# IVC_INTEGRATOR.net
KiCad netlist of a schematic drawn in Altium Designer
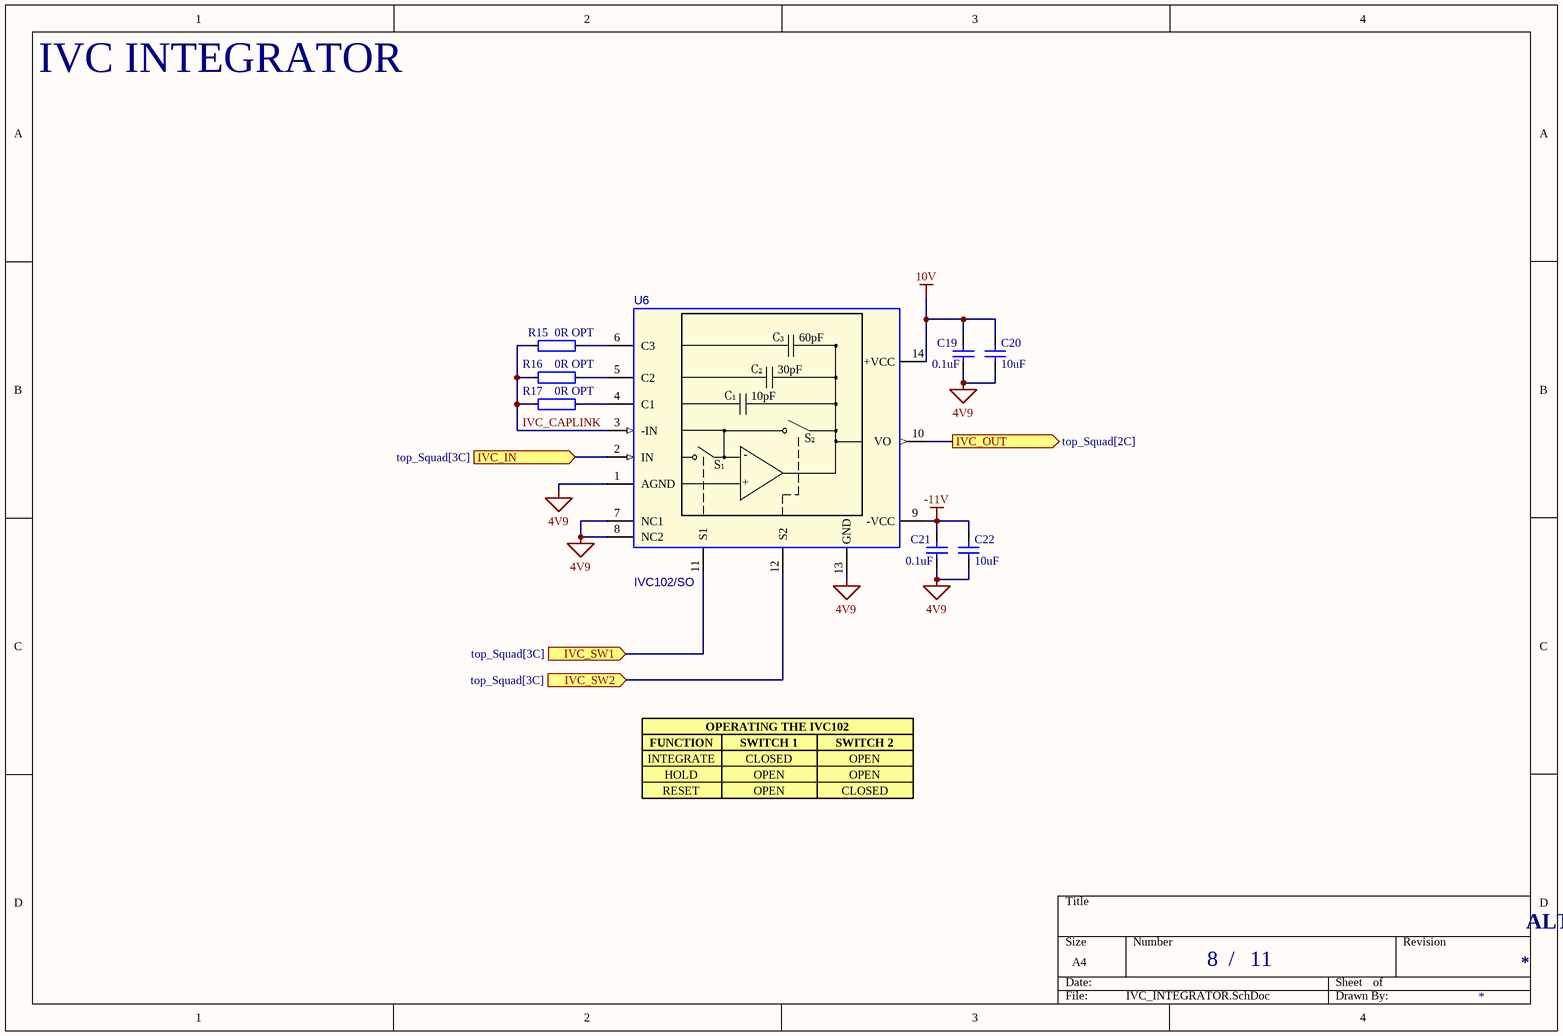
[diagram p0: IVC_INTEGRATOR.SchDoc]

(export (version "E")
  (design (tool "Eeschema 10.0.6"))
  (components
    (comp (ref "C19")
      (value "0.1uF")
      (footprint "CAP 0603 NON-IPC KEMET X7R")
      (description "Kemet C0603C104K5RACAUTO - Cap Ceramic 0.1uF 50V X7R 10% 0603 125C Paper T/R")
      (fields (field (name "MF") "Kemet") (field (name "MP") "C0603C104K5RACAUTO"))
      (libsource (lib "ALTAIR_PD_Capacitors") (part "CAP"))
    )
    (comp (ref "C20")
      (value "10uF")
      (footprint "CAP 0805 IPC MID DENSITY")
      (description "Murata GRM21BR61E106KA73L - Cap Ceramic 10uF 10% 25V X5R 0805")
      (fields (field (name "MF") "Murata") (field (name "MP") "GRM21BR61E106KA73L"))
      (libsource (lib "ALTAIR_PD_Capacitors") (part "CAP"))
    )
    (comp (ref "C21")
      (value "0.1uF")
      (footprint "CAP 0603 NON-IPC KEMET X7R")
      (description "Kemet C0603C104K5RACAUTO - Cap Ceramic 0.1uF 50V X7R 10% 0603 125C Paper T/R")
      (fields (field (name "MF") "Kemet") (field (name "MP") "C0603C104K5RACAUTO"))
      (libsource (lib "ALTAIR_PD_Capacitors") (part "CAP"))
    )
    (comp (ref "C22")
      (value "10uF")
      (footprint "CAP 0805 IPC MID DENSITY")
      (description "Murata GRM21BR61E106KA73L - Cap Ceramic 10uF 10% 25V X5R 0805")
      (fields (field (name "MF") "Murata") (field (name "MP") "GRM21BR61E106KA73L"))
      (libsource (lib "ALTAIR_PD_Capacitors") (part "CAP"))
    )
    (comp (ref "R15")
      (value "0R OPT")
      (footprint "RES 0402 IPC LOW DENSITY")
      (description "Yageo RC0402JR-070RL - Res 0 Ohms 1/16W SMD 0402")
      (fields (field (name "MF") "YAGEO") (field (name "MP") "RC0402JR-070RL"))
      (libsource (lib "ALTAIR_PD_Resistors") (part "IMPEDANCE"))
    )
    (comp (ref "R16")
      (value "0R OPT")
      (footprint "RES 0402 IPC LOW DENSITY")
      (description "Yageo RC0402JR-070RL - Res 0 Ohms 1/16W SMD 0402")
      (fields (field (name "MF") "YAGEO") (field (name "MP") "RC0402JR-070RL"))
      (libsource (lib "ALTAIR_PD_Resistors") (part "IMPEDANCE"))
    )
    (comp (ref "R17")
      (value "0R OPT")
      (footprint "RES 0402 IPC LOW DENSITY")
      (description "Yageo RC0402JR-070RL - Res 0 Ohms 1/16W SMD 0402")
      (fields (field (name "MF") "YAGEO") (field (name "MP") "RC0402JR-070RL"))
      (libsource (lib "ALTAIR_PD_Resistors") (part "IMPEDANCE"))
    )
    (comp (ref "U6")
      (value "IVC102/SO")
      (footprint "14-SOIC 4MM WIDE LOW DENSITY")
      (description "Precision Switched Integrator Transimpedance Amplifier")
      (fields (field (name "MF") "Texas Instruments") (field (name "MP") "IVC102U"))
      (libsource (lib "ALTAIR_PD_Amplifiers") (part "IVC102/SO_5"))
    )
  )
  (nets
    (net (code "1") (name "-11V") (class "Default")
      (node (ref "C21") (pin "2") (pinfunction "2_2") (pintype "passive"))
      (node (ref "C22") (pin "2") (pinfunction "2_2") (pintype "passive"))
      (node (ref "U6") (pin "9") (pinfunction "-VCC_9") (pintype "power_in"))
    )
    (net (code "2") (name "/IVC_CAPLINK") (class "Default")
      (node (ref "R15") (pin "1") (pinfunction "1_1") (pintype "passive"))
      (node (ref "R16") (pin "1") (pinfunction "1_1") (pintype "passive"))
      (node (ref "R17") (pin "1") (pinfunction "1_1") (pintype "passive"))
      (node (ref "U6") (pin "3") (pinfunction "-IN_3") (pintype "input"))
    )
    (net (code "3") (name "/IVC_IN") (class "Default")
      (node (ref "U6") (pin "2") (pinfunction "IN_2") (pintype "input"))
    )
    (net (code "4") (name "/IVC_OUT") (class "Default")
      (node (ref "U6") (pin "10") (pinfunction "VO_10") (pintype "output"))
    )
    (net (code "5") (name "/IVC_SW1") (class "Default")
      (node (ref "U6") (pin "11") (pinfunction "S1_11") (pintype "passive"))
    )
    (net (code "6") (name "/IVC_SW2") (class "Default")
      (node (ref "U6") (pin "12") (pinfunction "S2_12") (pintype "passive"))
    )
    (net (code "7") (name "4V9") (class "Default")
      (node (ref "C19") (pin "1") (pinfunction "1_1") (pintype "passive"))
      (node (ref "C20") (pin "1") (pinfunction "1_1") (pintype "passive"))
      (node (ref "C21") (pin "1") (pinfunction "1_1") (pintype "passive"))
      (node (ref "C22") (pin "1") (pinfunction "1_1") (pintype "passive"))
      (node (ref "U6") (pin "1") (pinfunction "AGND_1") (pintype "power_in"))
      (node (ref "U6") (pin "13") (pinfunction "GND_13") (pintype "power_in"))
      (node (ref "U6") (pin "7") (pinfunction "NC1_7") (pintype "passive"))
      (node (ref "U6") (pin "8") (pinfunction "NC2_8") (pintype "passive"))
    )
    (net (code "8") (name "10V") (class "Default")
      (node (ref "C19") (pin "2") (pinfunction "2_2") (pintype "passive"))
      (node (ref "C20") (pin "2") (pinfunction "2_2") (pintype "passive"))
      (node (ref "U6") (pin "14") (pinfunction "+VCC_14") (pintype "power_in"))
    )
    (net (code "9") (name "Net-(U6-C1)") (class "Default")
      (node (ref "R17") (pin "2") (pinfunction "2_2") (pintype "passive"))
      (node (ref "U6") (pin "4") (pinfunction "C1_4") (pintype "passive"))
    )
    (net (code "10") (name "Net-(U6-C2)") (class "Default")
      (node (ref "R16") (pin "2") (pinfunction "2_2") (pintype "passive"))
      (node (ref "U6") (pin "5") (pinfunction "C2_5") (pintype "passive"))
    )
    (net (code "11") (name "Net-(U6-C3)") (class "Default")
      (node (ref "R15") (pin "2") (pinfunction "2_2") (pintype "passive"))
      (node (ref "U6") (pin "6") (pinfunction "C3_6") (pintype "passive"))
    )
  )
)
